# STM32_Motherboard_2.net
KiCad netlist of a schematic drawn in Altium Designer
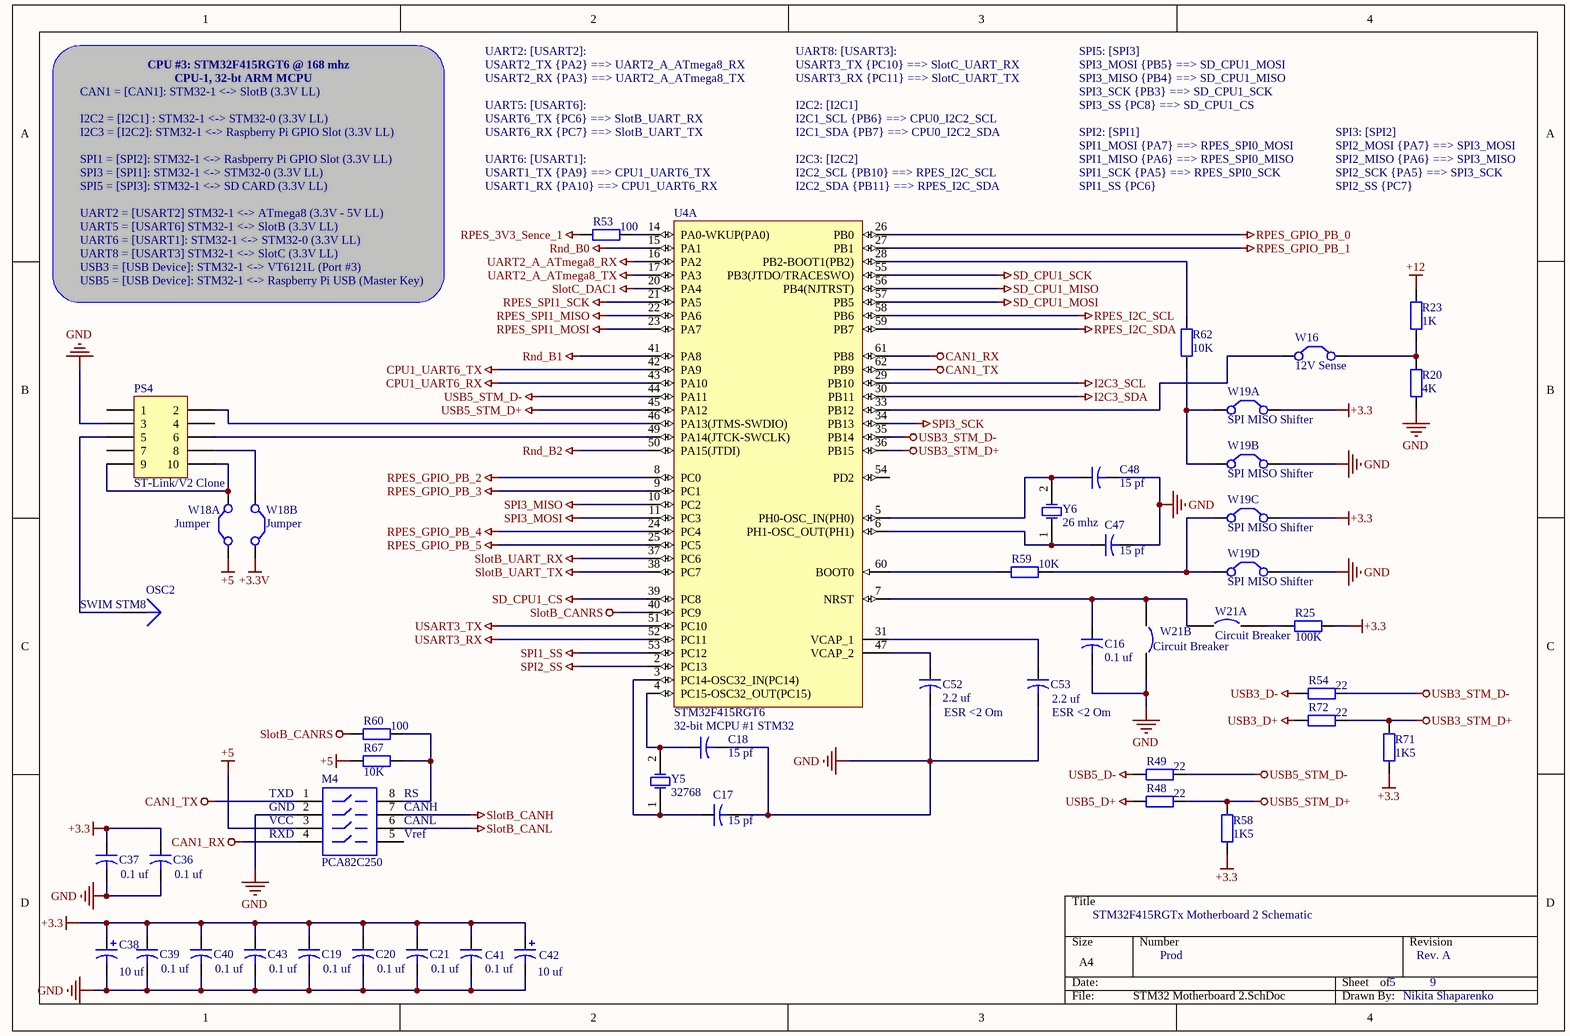
[diagram p0: STM32 Motherboard 2.SchDoc]

(export (version "E")
  (design (tool "Eeschema 10.0.6"))
  (components
    (comp (ref "C16")
      (value "0.1 uf")
      (footprint "CAPR5-4X5")
      (description "Capacitor")
      (fields (field (name "Comment") "Cap2") (field (name "PUBLISHER") "Altium Limited"))
      (libsource (lib "Miscellaneous Devices") (part "Cap2"))
    )
    (comp (ref "C17")
      (value "15 pf")
      (footprint "CAPR5-4X5")
      (description "Capacitor")
      (fields (field (name "Comment") "Cap2") (field (name "PUBLISHER") "Altium Limited"))
      (libsource (lib "Miscellaneous Devices") (part "Cap2"))
    )
    (comp (ref "C18")
      (value "15 pf")
      (footprint "CAPR5-4X5")
      (description "Capacitor")
      (fields (field (name "Comment") "Cap2") (field (name "PUBLISHER") "Altium Limited"))
      (libsource (lib "Miscellaneous Devices") (part "Cap2"))
    )
    (comp (ref "C19")
      (value "0.1 uf")
      (footprint "CAPR5-4X5")
      (description "Capacitor")
      (fields (field (name "Comment") "Cap2") (field (name "PUBLISHER") "Altium Limited"))
      (libsource (lib "Miscellaneous Devices") (part "Cap2"))
    )
    (comp (ref "C20")
      (value "0.1 uf")
      (footprint "CAPR5-4X5")
      (description "Capacitor")
      (fields (field (name "Comment") "Cap2") (field (name "PUBLISHER") "Altium Limited"))
      (libsource (lib "Miscellaneous Devices") (part "Cap2"))
    )
    (comp (ref "C21")
      (value "0.1 uf")
      (footprint "CAPR5-4X5")
      (description "Capacitor")
      (fields (field (name "Comment") "Cap2") (field (name "PUBLISHER") "Altium Limited"))
      (libsource (lib "Miscellaneous Devices") (part "Cap2"))
    )
    (comp (ref "C36")
      (value "0.1 uf")
      (footprint "CAPR5-4X5")
      (description "Capacitor")
      (fields (field (name "Comment") "Cap2") (field (name "PUBLISHER") "Altium Limited"))
      (libsource (lib "Miscellaneous Devices") (part "Cap2"))
    )
    (comp (ref "C37")
      (value "0.1 uf")
      (footprint "CAPR5-4X5")
      (description "Capacitor")
      (fields (field (name "Comment") "Cap2") (field (name "PUBLISHER") "Altium Limited"))
      (libsource (lib "Miscellaneous Devices") (part "Cap2"))
    )
    (comp (ref "C38")
      (value "10 uf")
      (footprint "RAD-0.2")
      (description "Polarized Capacitor (Radial)")
      (fields (field (name "Comment") "Cap Pol1") (field (name "PUBLISHER") "Altium Limited"))
      (libsource (lib "Miscellaneous Devices") (part "Cap Pol1"))
    )
    (comp (ref "C39")
      (value "0.1 uf")
      (footprint "CAPR5-4X5")
      (description "Capacitor")
      (fields (field (name "Comment") "Cap2") (field (name "PUBLISHER") "Altium Limited"))
      (libsource (lib "Miscellaneous Devices") (part "Cap2"))
    )
    (comp (ref "C40")
      (value "0.1 uf")
      (footprint "CAPR5-4X5")
      (description "Capacitor")
      (fields (field (name "Comment") "Cap2") (field (name "PUBLISHER") "Altium Limited"))
      (libsource (lib "Miscellaneous Devices") (part "Cap2"))
    )
    (comp (ref "C41")
      (value "0.1 uf")
      (footprint "CAPR5-4X5")
      (description "Capacitor")
      (fields (field (name "Comment") "Cap2") (field (name "PUBLISHER") "Altium Limited"))
      (libsource (lib "Miscellaneous Devices") (part "Cap2"))
    )
    (comp (ref "C42")
      (value "10 uf")
      (footprint "RAD-0.2")
      (description "Polarized Capacitor (Radial)")
      (fields (field (name "Comment") "Cap Pol1") (field (name "PUBLISHER") "Altium Limited"))
      (libsource (lib "Miscellaneous Devices") (part "Cap Pol1"))
    )
    (comp (ref "C43")
      (value "0.1 uf")
      (footprint "CAPR5-4X5")
      (description "Capacitor")
      (fields (field (name "Comment") "Cap2") (field (name "PUBLISHER") "Altium Limited"))
      (libsource (lib "Miscellaneous Devices") (part "Cap2"))
    )
    (comp (ref "C47")
      (value "15 pf")
      (footprint "CAPR5-4X5")
      (description "Capacitor")
      (fields (field (name "Comment") "Cap2") (field (name "PUBLISHER") "Altium Limited"))
      (libsource (lib "Miscellaneous Devices") (part "Cap2"))
    )
    (comp (ref "C48")
      (value "15 pf")
      (footprint "CAPR5-4X5")
      (description "Capacitor")
      (fields (field (name "Comment") "Cap2") (field (name "PUBLISHER") "Altium Limited"))
      (libsource (lib "Miscellaneous Devices") (part "Cap2"))
    )
    (comp (ref "C52")
      (value "ESR <2 Om")
      (footprint "CAPR5-4X5")
      (description "Capacitor")
      (fields (field (name "ALTIUM_VALUE") "2.2 uf") (field (name "PUBLISHER") "Altium Limited"))
      (libsource (lib "Miscellaneous Devices") (part "Cap2"))
    )
    (comp (ref "C53")
      (value "ESR <2 Om")
      (footprint "CAPR5-4X5")
      (description "Capacitor")
      (fields (field (name "ALTIUM_VALUE") "2.2 uf") (field (name "PUBLISHER") "Altium Limited"))
      (libsource (lib "Miscellaneous Devices") (part "Cap2"))
    )
    (comp (ref "M4")
      (value "PCA82C250")
      (footprint "8S1_N")
      (description "DIP Switch")
      (fields (field (name "PUBLISHER") "Altium Limited"))
      (libsource (lib "Miscellaneous Devices") (part "SW-DIP4"))
    )
    (comp (ref "OSC2")
      (value "SWIM STM8")
      (footprint "PIN1")
      (description "Plug")
      (fields (field (name "PUBLISHER") "Altium Limited"))
      (libsource (lib "Miscellaneous Connectors") (part "Plug"))
    )
    (comp (ref "PS4")
      (value "ST-Link/V2 Clone")
      (footprint "HDR2X5")
      (description "Header, 5-Pin, Dual row")
      (fields (field (name "PUBLISHER") "Altium Limited"))
      (libsource (lib "Miscellaneous Connectors") (part "Header 5X2"))
    )
    (comp (ref "R20")
      (value "4K")
      (footprint "AXIAL-0.4")
      (description "Resistor")
      (fields (field (name "Comment") "Res2") (field (name "PUBLISHER") "Altium Limited"))
      (libsource (lib "") (part "Res2_2"))
    )
    (comp (ref "R23")
      (value "1K")
      (footprint "AXIAL-0.4")
      (description "Resistor")
      (fields (field (name "Comment") "Res2") (field (name "PUBLISHER") "Altium Limited"))
      (libsource (lib "") (part "Res2_2"))
    )
    (comp (ref "R25")
      (value "100K")
      (footprint "AXIAL-0.4")
      (description "Resistor")
      (fields (field (name "Comment") "Res2") (field (name "PUBLISHER") "Altium Limited"))
      (libsource (lib "") (part "Res2_1"))
    )
    (comp (ref "R48")
      (value "22")
      (footprint "AXIAL-0.4")
      (description "Resistor")
      (fields (field (name "Comment") "Res2") (field (name "PUBLISHER") "Altium Limited"))
      (libsource (lib "Miscellaneous Devices") (part "Res2"))
    )
    (comp (ref "R49")
      (value "22")
      (footprint "AXIAL-0.4")
      (description "Resistor")
      (fields (field (name "Comment") "Res2") (field (name "PUBLISHER") "Altium Limited"))
      (libsource (lib "Miscellaneous Devices") (part "Res2"))
    )
    (comp (ref "R53")
      (value "100")
      (footprint "AXIAL-0.4")
      (description "Resistor")
      (fields (field (name "Comment") "Res2") (field (name "PUBLISHER") "Altium Limited"))
      (libsource (lib "Miscellaneous Devices") (part "Res2"))
    )
    (comp (ref "R54")
      (value "22")
      (footprint "AXIAL-0.4")
      (description "Resistor")
      (fields (field (name "Comment") "Res2") (field (name "PUBLISHER") "Altium Limited"))
      (libsource (lib "Miscellaneous Devices") (part "Res2"))
    )
    (comp (ref "R58")
      (value "1K5")
      (footprint "AXIAL-0.4")
      (description "Resistor")
      (fields (field (name "Comment") "Res2") (field (name "PUBLISHER") "Altium Limited"))
      (libsource (lib "") (part "Res2_2"))
    )
    (comp (ref "R59")
      (value "10K")
      (footprint "AXIAL-0.4")
      (description "Resistor")
      (fields (field (name "Comment") "Res2") (field (name "PUBLISHER") "Altium Limited"))
      (libsource (lib "Miscellaneous Devices") (part "Res2"))
    )
    (comp (ref "R60")
      (value "100")
      (footprint "AXIAL-0.4")
      (description "Resistor")
      (fields (field (name "Comment") "Res2") (field (name "PUBLISHER") "Altium Limited"))
      (libsource (lib "Miscellaneous Devices") (part "Res2"))
    )
    (comp (ref "R62")
      (value "10K")
      (footprint "AXIAL-0.4")
      (description "Resistor")
      (fields (field (name "Comment") "Res2") (field (name "PUBLISHER") "Altium Limited"))
      (libsource (lib "") (part "Res2_2"))
    )
    (comp (ref "R67")
      (value "10K")
      (footprint "AXIAL-0.4")
      (description "Resistor")
      (fields (field (name "Comment") "Res2") (field (name "PUBLISHER") "Altium Limited"))
      (libsource (lib "") (part "Res2_1"))
    )
    (comp (ref "R71")
      (value "1K5")
      (footprint "AXIAL-0.4")
      (description "Resistor")
      (fields (field (name "Comment") "Res2") (field (name "PUBLISHER") "Altium Limited"))
      (libsource (lib "") (part "Res2_2"))
    )
    (comp (ref "R72")
      (value "22")
      (footprint "AXIAL-0.4")
      (description "Resistor")
      (fields (field (name "Comment") "Res2") (field (name "PUBLISHER") "Altium Limited"))
      (libsource (lib "Miscellaneous Devices") (part "Res2"))
    )
    (comp (ref "U4")
      (value "STM32F415RGT6")
      (footprint "STM-LQFP64_N")
      (fields (field (name "MANUFACTURER") "STMicroelectronics"))
      (libsource (lib "STMicroelectronics STM32 F4") (part "STM32F415RGT6"))
    )
    (comp (ref "W16")
      (value "12V Sense")
      (footprint "RAD-0.1")
      (description "Jumper Wire")
      (fields (field (name "PUBLISHER") "Altium Limited"))
      (libsource (lib "Miscellaneous Devices") (part "Jumper"))
    )
    (comp (ref "W18A")
      (value "Jumper")
      (footprint "RAD-0.1")
      (description "Jumper Wire")
      (fields (field (name "PUBLISHER") "Altium Limited"))
      (libsource (lib "Miscellaneous Devices") (part "Jumper"))
    )
    (comp (ref "W18B")
      (value "Jumper")
      (footprint "RAD-0.1")
      (description "Jumper Wire")
      (fields (field (name "PUBLISHER") "Altium Limited"))
      (libsource (lib "Miscellaneous Devices") (part "Jumper"))
    )
    (comp (ref "W19A")
      (value "SPI MISO Shifter")
      (footprint "RAD-0.1")
      (description "Jumper Wire")
      (fields (field (name "PUBLISHER") "Altium Limited"))
      (libsource (lib "Miscellaneous Devices") (part "Jumper"))
    )
    (comp (ref "W19B")
      (value "SPI MISO Shifter")
      (footprint "RAD-0.1")
      (description "Jumper Wire")
      (fields (field (name "PUBLISHER") "Altium Limited"))
      (libsource (lib "Miscellaneous Devices") (part "Jumper"))
    )
    (comp (ref "W19C")
      (value "SPI MISO Shifter")
      (footprint "RAD-0.1")
      (description "Jumper Wire")
      (fields (field (name "PUBLISHER") "Altium Limited"))
      (libsource (lib "Miscellaneous Devices") (part "Jumper"))
    )
    (comp (ref "W19D")
      (value "SPI MISO Shifter")
      (footprint "RAD-0.1")
      (description "Jumper Wire")
      (fields (field (name "PUBLISHER") "Altium Limited"))
      (libsource (lib "Miscellaneous Devices") (part "Jumper"))
    )
    (comp (ref "W21A")
      (value "Circuit Breaker")
      (footprint "SPST-2")
      (fields (field (name "PUBLISHER") "Altium Limited"))
      (libsource (lib "Miscellaneous Devices") (part "Circuit Breaker"))
    )
    (comp (ref "W21B")
      (value "Circuit Breaker")
      (footprint "SPST-2")
      (fields (field (name "PUBLISHER") "Altium Limited"))
      (libsource (lib "Miscellaneous Devices") (part "Circuit Breaker"))
    )
    (comp (ref "Y5")
      (value "32768")
      (footprint "R38")
      (description "Crystal Oscillator")
      (fields (field (name "PUBLISHER") "Altium Limited"))
      (libsource (lib "Miscellaneous Devices") (part "XTAL"))
    )
    (comp (ref "Y6")
      (value "26 mhz")
      (footprint "R38")
      (description "Crystal Oscillator")
      (fields (field (name "PUBLISHER") "Altium Limited"))
      (libsource (lib "Miscellaneous Devices") (part "XTAL"))
    )
  )
  (nets
    (net (code "1") (name "+3.3") (class "Default")
      (node (ref "C19") (pin "1") (pinfunction "1_1") (pintype "passive"))
      (node (ref "C20") (pin "1") (pinfunction "1_1") (pintype "passive"))
      (node (ref "C21") (pin "1") (pinfunction "1_1") (pintype "passive"))
      (node (ref "C36") (pin "1") (pinfunction "1_1") (pintype "passive"))
      (node (ref "C37") (pin "1") (pinfunction "1_1") (pintype "passive"))
      (node (ref "C38") (pin "1") (pinfunction "1_1") (pintype "passive"))
      (node (ref "C39") (pin "1") (pinfunction "1_1") (pintype "passive"))
      (node (ref "C40") (pin "1") (pinfunction "1_1") (pintype "passive"))
      (node (ref "C41") (pin "1") (pinfunction "1_1") (pintype "passive"))
      (node (ref "C42") (pin "1") (pinfunction "1_1") (pintype "passive"))
      (node (ref "C43") (pin "1") (pinfunction "1_1") (pintype "passive"))
      (node (ref "R25") (pin "1") (pinfunction "1_1") (pintype "passive"))
      (node (ref "R58") (pin "1") (pinfunction "1_1") (pintype "passive"))
      (node (ref "R71") (pin "1") (pinfunction "1_1") (pintype "passive"))
      (node (ref "W19A") (pin "2") (pinfunction "C2_2") (pintype "passive"))
      (node (ref "W19C") (pin "2") (pinfunction "C2_2") (pintype "passive"))
    )
    (net (code "2") (name "+3.3V") (class "Default")
      (node (ref "W18B") (pin "2") (pinfunction "C2_2") (pintype "passive"))
    )
    (net (code "3") (name "+5") (class "Default")
      (node (ref "M4") (pin "3") (pinfunction "3_3") (pintype "passive"))
      (node (ref "R67") (pin "2") (pinfunction "2_2") (pintype "passive"))
      (node (ref "W18A") (pin "1") (pinfunction "C1_1") (pintype "passive"))
    )
    (net (code "4") (name "+12") (class "Default")
      (node (ref "R23") (pin "2") (pinfunction "2_2") (pintype "passive"))
    )
    (net (code "5") (name "CAN1_RX") (class "Default")
      (node (ref "M4") (pin "4") (pinfunction "4_4") (pintype "passive"))
      (node (ref "U4") (pin "61") (pinfunction "PB8_61") (pintype "bidirectional"))
    )
    (net (code "6") (name "CAN1_TX") (class "Default")
      (node (ref "M4") (pin "1") (pinfunction "1_1") (pintype "passive"))
      (node (ref "U4") (pin "62") (pinfunction "PB9_62") (pintype "bidirectional"))
    )
    (net (code "7") (name "CPU1_UART6_RX") (class "Default")
      (node (ref "U4") (pin "43") (pinfunction "PA10_43") (pintype "bidirectional"))
    )
    (net (code "8") (name "CPU1_UART6_TX") (class "Default")
      (node (ref "U4") (pin "42") (pinfunction "PA9_42") (pintype "bidirectional"))
    )
    (net (code "9") (name "GND") (class "Default")
      (node (ref "C16") (pin "2") (pinfunction "2_2") (pintype "passive"))
      (node (ref "C17") (pin "2") (pinfunction "2_2") (pintype "passive"))
      (node (ref "C18") (pin "2") (pinfunction "2_2") (pintype "passive"))
      (node (ref "C19") (pin "2") (pinfunction "2_2") (pintype "passive"))
      (node (ref "C20") (pin "2") (pinfunction "2_2") (pintype "passive"))
      (node (ref "C21") (pin "2") (pinfunction "2_2") (pintype "passive"))
      (node (ref "C36") (pin "2") (pinfunction "2_2") (pintype "passive"))
      (node (ref "C37") (pin "2") (pinfunction "2_2") (pintype "passive"))
      (node (ref "C38") (pin "2") (pinfunction "2_2") (pintype "passive"))
      (node (ref "C39") (pin "2") (pinfunction "2_2") (pintype "passive"))
      (node (ref "C40") (pin "2") (pinfunction "2_2") (pintype "passive"))
      (node (ref "C41") (pin "2") (pinfunction "2_2") (pintype "passive"))
      (node (ref "C42") (pin "2") (pinfunction "2_2") (pintype "passive"))
      (node (ref "C43") (pin "2") (pinfunction "2_2") (pintype "passive"))
      (node (ref "C47") (pin "2") (pinfunction "2_2") (pintype "passive"))
      (node (ref "C48") (pin "2") (pinfunction "2_2") (pintype "passive"))
      (node (ref "C52") (pin "2") (pinfunction "2_2") (pintype "passive"))
      (node (ref "C53") (pin "2") (pinfunction "2_2") (pintype "passive"))
      (node (ref "M4") (pin "2") (pinfunction "2_2") (pintype "passive"))
      (node (ref "PS4") (pin "3") (pinfunction "3_3") (pintype "passive"))
      (node (ref "R20") (pin "1") (pinfunction "1_1") (pintype "passive"))
      (node (ref "W19B") (pin "2") (pinfunction "C2_2") (pintype "passive"))
      (node (ref "W19D") (pin "2") (pinfunction "C2_2") (pintype "passive"))
      (node (ref "W21B") (pin "2") (pinfunction "2_2") (pintype "passive"))
    )
    (net (code "10") (name "I2C3_SCL") (class "Default")
      (node (ref "U4") (pin "29") (pinfunction "PB10_29") (pintype "bidirectional"))
    )
    (net (code "11") (name "I2C3_SDA") (class "Default")
      (node (ref "U4") (pin "30") (pinfunction "PB11_30") (pintype "bidirectional"))
    )
    (net (code "12") (name "Net-(M4-Pad8)") (class "Default")
      (node (ref "M4") (pin "8") (pinfunction "8_8") (pintype "passive"))
      (node (ref "R60") (pin "2") (pinfunction "2_2") (pintype "passive"))
      (node (ref "R67") (pin "1") (pinfunction "1_1") (pintype "passive"))
    )
    (net (code "13") (name "Net-(OSC2-Pad1)") (class "Default")
      (node (ref "OSC2") (pin "1") (pinfunction "1_1") (pintype "passive"))
      (node (ref "PS4") (pin "5") (pinfunction "5_5") (pintype "passive"))
    )
    (net (code "14") (name "Net-(R25-Pad2)") (class "Default")
      (node (ref "R25") (pin "2") (pinfunction "2_2") (pintype "passive"))
      (node (ref "W21A") (pin "2") (pinfunction "2_2") (pintype "passive"))
    )
    (net (code "15") (name "Net-(U4A-BOOT0)") (class "Default")
      (node (ref "R59") (pin "1") (pinfunction "1_1") (pintype "passive"))
      (node (ref "U4") (pin "60") (pinfunction "BOOT0_60") (pintype "input"))
    )
    (net (code "16") (name "Net-(U4A-NRST)") (class "Default")
      (node (ref "C16") (pin "1") (pinfunction "1_1") (pintype "passive"))
      (node (ref "U4") (pin "7") (pinfunction "NRST_7") (pintype "bidirectional"))
      (node (ref "W21A") (pin "1") (pinfunction "1_1") (pintype "passive"))
      (node (ref "W21B") (pin "1") (pinfunction "1_1") (pintype "passive"))
    )
    (net (code "17") (name "Net-(U4A-PA0-WKUP(PA0))") (class "Default")
      (node (ref "R53") (pin "2") (pinfunction "2_2") (pintype "passive"))
      (node (ref "U4") (pin "14") (pinfunction "PA0-WKUP(PA0)_14") (pintype "bidirectional"))
    )
    (net (code "18") (name "Net-(U4A-PA13(JTMS-SWDIO))") (class "Default")
      (node (ref "PS4") (pin "2") (pinfunction "2_2") (pintype "passive"))
      (node (ref "U4") (pin "46") (pinfunction "PA13(JTMS-SWDIO)_46") (pintype "bidirectional"))
    )
    (net (code "19") (name "Net-(U4A-PA14(JTCK-SWCLK))") (class "Default")
      (node (ref "PS4") (pin "6") (pinfunction "6_6") (pintype "passive"))
      (node (ref "U4") (pin "49") (pinfunction "PA14(JTCK-SWCLK)_49") (pintype "bidirectional"))
    )
    (net (code "20") (name "Net-(U4A-PB2-BOOT1(PB2))") (class "Default")
      (node (ref "R62") (pin "2") (pinfunction "2_2") (pintype "passive"))
      (node (ref "U4") (pin "28") (pinfunction "PB2-BOOT1(PB2)_28") (pintype "bidirectional"))
    )
    (net (code "21") (name "Net-(U4A-PB12)") (class "Default")
      (node (ref "U4") (pin "33") (pinfunction "PB12_33") (pintype "bidirectional"))
      (node (ref "W16") (pin "1") (pinfunction "C1_1") (pintype "passive"))
    )
    (net (code "22") (name "Net-(U4A-PC14-OSC32_IN(PC14))") (class "Default")
      (node (ref "C17") (pin "1") (pinfunction "1_1") (pintype "passive"))
      (node (ref "U4") (pin "3") (pinfunction "PC14-OSC32_IN(PC14)_3") (pintype "bidirectional"))
      (node (ref "Y5") (pin "1") (pinfunction "OSC1_1") (pintype "passive"))
    )
    (net (code "23") (name "Net-(U4A-PC15-OSC32_OUT(PC15))") (class "Default")
      (node (ref "C18") (pin "1") (pinfunction "1_1") (pintype "passive"))
      (node (ref "U4") (pin "4") (pinfunction "PC15-OSC32_OUT(PC15)_4") (pintype "bidirectional"))
      (node (ref "Y5") (pin "2") (pinfunction "OSC2_2") (pintype "passive"))
    )
    (net (code "24") (name "Net-(U4A-PH0-OSC_IN(PH0))") (class "Default")
      (node (ref "C48") (pin "1") (pinfunction "1_1") (pintype "passive"))
      (node (ref "U4") (pin "5") (pinfunction "PH0-OSC_IN(PH0)_5") (pintype "bidirectional"))
      (node (ref "Y6") (pin "2") (pinfunction "OSC2_2") (pintype "passive"))
    )
    (net (code "25") (name "Net-(U4A-PH1-OSC_OUT(PH1))") (class "Default")
      (node (ref "C47") (pin "1") (pinfunction "1_1") (pintype "passive"))
      (node (ref "U4") (pin "6") (pinfunction "PH1-OSC_OUT(PH1)_6") (pintype "bidirectional"))
      (node (ref "Y6") (pin "1") (pinfunction "OSC1_1") (pintype "passive"))
    )
    (net (code "26") (name "Net-(U4A-VCAP_1)") (class "Default")
      (node (ref "C53") (pin "1") (pinfunction "1_1") (pintype "passive"))
      (node (ref "U4") (pin "31") (pinfunction "VCAP_1_31") (pintype "power_in"))
    )
    (net (code "27") (name "Net-(U4A-VCAP_2)") (class "Default")
      (node (ref "C52") (pin "1") (pinfunction "1_1") (pintype "passive"))
      (node (ref "U4") (pin "47") (pinfunction "VCAP_2_47") (pintype "power_in"))
    )
    (net (code "28") (name "Net-(W16-C2)") (class "Default")
      (node (ref "R20") (pin "2") (pinfunction "2_2") (pintype "passive"))
      (node (ref "R23") (pin "1") (pinfunction "1_1") (pintype "passive"))
      (node (ref "W16") (pin "2") (pinfunction "C2_2") (pintype "passive"))
    )
    (net (code "29") (name "Net-(W18A-C2)") (class "Default")
      (node (ref "PS4") (pin "10") (pinfunction "10_10") (pintype "passive"))
      (node (ref "PS4") (pin "9") (pinfunction "9_9") (pintype "passive"))
      (node (ref "W18A") (pin "2") (pinfunction "C2_2") (pintype "passive"))
    )
    (net (code "30") (name "Net-(W18B-C1)") (class "Default")
      (node (ref "PS4") (pin "8") (pinfunction "8_8") (pintype "passive"))
      (node (ref "W18B") (pin "1") (pinfunction "C1_1") (pintype "passive"))
    )
    (net (code "31") (name "Net-(W19A-C1)") (class "Default")
      (node (ref "R62") (pin "1") (pinfunction "1_1") (pintype "passive"))
      (node (ref "W19A") (pin "1") (pinfunction "C1_1") (pintype "passive"))
      (node (ref "W19B") (pin "1") (pinfunction "C1_1") (pintype "passive"))
    )
    (net (code "32") (name "Net-(W19C-C1)") (class "Default")
      (node (ref "R59") (pin "2") (pinfunction "2_2") (pintype "passive"))
      (node (ref "W19C") (pin "1") (pinfunction "C1_1") (pintype "passive"))
      (node (ref "W19D") (pin "1") (pinfunction "C1_1") (pintype "passive"))
    )
    (net (code "33") (name "RPES_3V3_Sence_1") (class "Default")
      (node (ref "R53") (pin "1") (pinfunction "1_1") (pintype "passive"))
    )
    (net (code "34") (name "RPES_GPIO_PB_0") (class "Default")
      (node (ref "U4") (pin "26") (pinfunction "PB0_26") (pintype "bidirectional"))
    )
    (net (code "35") (name "RPES_GPIO_PB_1") (class "Default")
      (node (ref "U4") (pin "27") (pinfunction "PB1_27") (pintype "bidirectional"))
    )
    (net (code "36") (name "RPES_GPIO_PB_2") (class "Default")
      (node (ref "U4") (pin "8") (pinfunction "PC0_8") (pintype "bidirectional"))
    )
    (net (code "37") (name "RPES_GPIO_PB_3") (class "Default")
      (node (ref "U4") (pin "9") (pinfunction "PC1_9") (pintype "bidirectional"))
    )
    (net (code "38") (name "RPES_GPIO_PB_4") (class "Default")
      (node (ref "U4") (pin "24") (pinfunction "PC4_24") (pintype "bidirectional"))
    )
    (net (code "39") (name "RPES_GPIO_PB_5") (class "Default")
      (node (ref "U4") (pin "25") (pinfunction "PC5_25") (pintype "bidirectional"))
    )
    (net (code "40") (name "RPES_I2C_SCL") (class "Default")
      (node (ref "U4") (pin "58") (pinfunction "PB6_58") (pintype "bidirectional"))
    )
    (net (code "41") (name "RPES_I2C_SDA") (class "Default")
      (node (ref "U4") (pin "59") (pinfunction "PB7_59") (pintype "bidirectional"))
    )
    (net (code "42") (name "RPES_SPI1_MISO") (class "Default")
      (node (ref "U4") (pin "22") (pinfunction "PA6_22") (pintype "bidirectional"))
    )
    (net (code "43") (name "RPES_SPI1_MOSI") (class "Default")
      (node (ref "U4") (pin "23") (pinfunction "PA7_23") (pintype "bidirectional"))
    )
    (net (code "44") (name "RPES_SPI1_SCK") (class "Default")
      (node (ref "U4") (pin "21") (pinfunction "PA5_21") (pintype "bidirectional"))
    )
    (net (code "45") (name "Rnd_B0") (class "Default")
      (node (ref "U4") (pin "15") (pinfunction "PA1_15") (pintype "bidirectional"))
    )
    (net (code "46") (name "Rnd_B1") (class "Default")
      (node (ref "U4") (pin "41") (pinfunction "PA8_41") (pintype "bidirectional"))
    )
    (net (code "47") (name "Rnd_B2") (class "Default")
      (node (ref "U4") (pin "50") (pinfunction "PA15(JTDI)_50") (pintype "bidirectional"))
    )
    (net (code "48") (name "SD_CPU1_CS") (class "Default")
      (node (ref "U4") (pin "39") (pinfunction "PC8_39") (pintype "bidirectional"))
    )
    (net (code "49") (name "SD_CPU1_MISO") (class "Default")
      (node (ref "U4") (pin "56") (pinfunction "PB4(NJTRST)_56") (pintype "bidirectional"))
    )
    (net (code "50") (name "SD_CPU1_MOSI") (class "Default")
      (node (ref "U4") (pin "57") (pinfunction "PB5_57") (pintype "bidirectional"))
    )
    (net (code "51") (name "SD_CPU1_SCK") (class "Default")
      (node (ref "U4") (pin "55") (pinfunction "PB3(JTDO/TRACESWO)_55") (pintype "bidirectional"))
    )
    (net (code "52") (name "SPI1_SS") (class "Default")
      (node (ref "U4") (pin "53") (pinfunction "PC12_53") (pintype "bidirectional"))
    )
    (net (code "53") (name "SPI2_SS") (class "Default")
      (node (ref "U4") (pin "2") (pinfunction "PC13_2") (pintype "bidirectional"))
    )
    (net (code "54") (name "SPI3_MISO") (class "Default")
      (node (ref "U4") (pin "10") (pinfunction "PC2_10") (pintype "bidirectional"))
    )
    (net (code "55") (name "SPI3_MOSI") (class "Default")
      (node (ref "U4") (pin "11") (pinfunction "PC3_11") (pintype "bidirectional"))
    )
    (net (code "56") (name "SPI3_SCK") (class "Default")
      (node (ref "U4") (pin "34") (pinfunction "PB13_34") (pintype "bidirectional"))
    )
    (net (code "57") (name "SlotB_CANH") (class "Default")
      (node (ref "M4") (pin "7") (pinfunction "7_7") (pintype "passive"))
    )
    (net (code "58") (name "SlotB_CANL") (class "Default")
      (node (ref "M4") (pin "6") (pinfunction "6_6") (pintype "passive"))
    )
    (net (code "59") (name "SlotB_CANRS") (class "Default")
      (node (ref "R60") (pin "1") (pinfunction "1_1") (pintype "passive"))
      (node (ref "U4") (pin "40") (pinfunction "PC9_40") (pintype "bidirectional"))
    )
    (net (code "60") (name "SlotB_UART_RX") (class "Default")
      (node (ref "U4") (pin "37") (pinfunction "PC6_37") (pintype "bidirectional"))
    )
    (net (code "61") (name "SlotB_UART_TX") (class "Default")
      (node (ref "U4") (pin "38") (pinfunction "PC7_38") (pintype "bidirectional"))
    )
    (net (code "62") (name "SlotC_DAC1") (class "Default")
      (node (ref "U4") (pin "20") (pinfunction "PA4_20") (pintype "bidirectional"))
    )
    (net (code "63") (name "UART2_A_ATmega8_RX") (class "Default")
      (node (ref "U4") (pin "16") (pinfunction "PA2_16") (pintype "bidirectional"))
    )
    (net (code "64") (name "UART2_A_ATmega8_TX") (class "Default")
      (node (ref "U4") (pin "17") (pinfunction "PA3_17") (pintype "bidirectional"))
    )
    (net (code "65") (name "USART3_RX") (class "Default")
      (node (ref "U4") (pin "52") (pinfunction "PC11_52") (pintype "bidirectional"))
    )
    (net (code "66") (name "USART3_TX") (class "Default")
      (node (ref "U4") (pin "51") (pinfunction "PC10_51") (pintype "bidirectional"))
    )
    (net (code "67") (name "USB3_D+") (class "Default")
      (node (ref "R72") (pin "1") (pinfunction "1_1") (pintype "passive"))
    )
    (net (code "68") (name "USB3_D-") (class "Default")
      (node (ref "R54") (pin "1") (pinfunction "1_1") (pintype "passive"))
    )
    (net (code "69") (name "USB3_STM_D+") (class "Default")
      (node (ref "R71") (pin "2") (pinfunction "2_2") (pintype "passive"))
      (node (ref "R72") (pin "2") (pinfunction "2_2") (pintype "passive"))
      (node (ref "U4") (pin "36") (pinfunction "PB15_36") (pintype "bidirectional"))
    )
    (net (code "70") (name "USB3_STM_D-") (class "Default")
      (node (ref "R54") (pin "2") (pinfunction "2_2") (pintype "passive"))
      (node (ref "U4") (pin "35") (pinfunction "PB14_35") (pintype "bidirectional"))
    )
    (net (code "71") (name "USB5_D+") (class "Default")
      (node (ref "R48") (pin "1") (pinfunction "1_1") (pintype "passive"))
    )
    (net (code "72") (name "USB5_D-") (class "Default")
      (node (ref "R49") (pin "1") (pinfunction "1_1") (pintype "passive"))
    )
    (net (code "73") (name "USB5_STM_D+") (class "Default")
      (node (ref "R48") (pin "2") (pinfunction "2_2") (pintype "passive"))
      (node (ref "R58") (pin "2") (pinfunction "2_2") (pintype "passive"))
      (node (ref "U4") (pin "45") (pinfunction "PA12_45") (pintype "bidirectional"))
    )
    (net (code "74") (name "USB5_STM_D-") (class "Default")
      (node (ref "R49") (pin "2") (pinfunction "2_2") (pintype "passive"))
      (node (ref "U4") (pin "44") (pinfunction "PA11_44") (pintype "bidirectional"))
    )
    (net (code "75") (name "unconnected-(M4-Pad5)") (class "Default")
      (node (ref "M4") (pin "5") (pinfunction "5_5") (pintype "passive"))
    )
    (net (code "76") (name "unconnected-(PS4-Pad1)") (class "Default")
      (node (ref "PS4") (pin "1") (pinfunction "1_1") (pintype "passive"))
    )
    (net (code "77") (name "unconnected-(PS4-Pad4)") (class "Default")
      (node (ref "PS4") (pin "4") (pinfunction "4_4") (pintype "passive"))
    )
    (net (code "78") (name "unconnected-(PS4-Pad7)") (class "Default")
      (node (ref "PS4") (pin "7") (pinfunction "7_7") (pintype "passive"))
    )
    (net (code "79") (name "unconnected-(U4A-PD2-Pad54)") (class "Default")
      (node (ref "U4") (pin "54") (pinfunction "PD2_54") (pintype "bidirectional"))
    )
  )
)
